# weather_station1.net
KiCad netlist of a schematic drawn in EAGLE
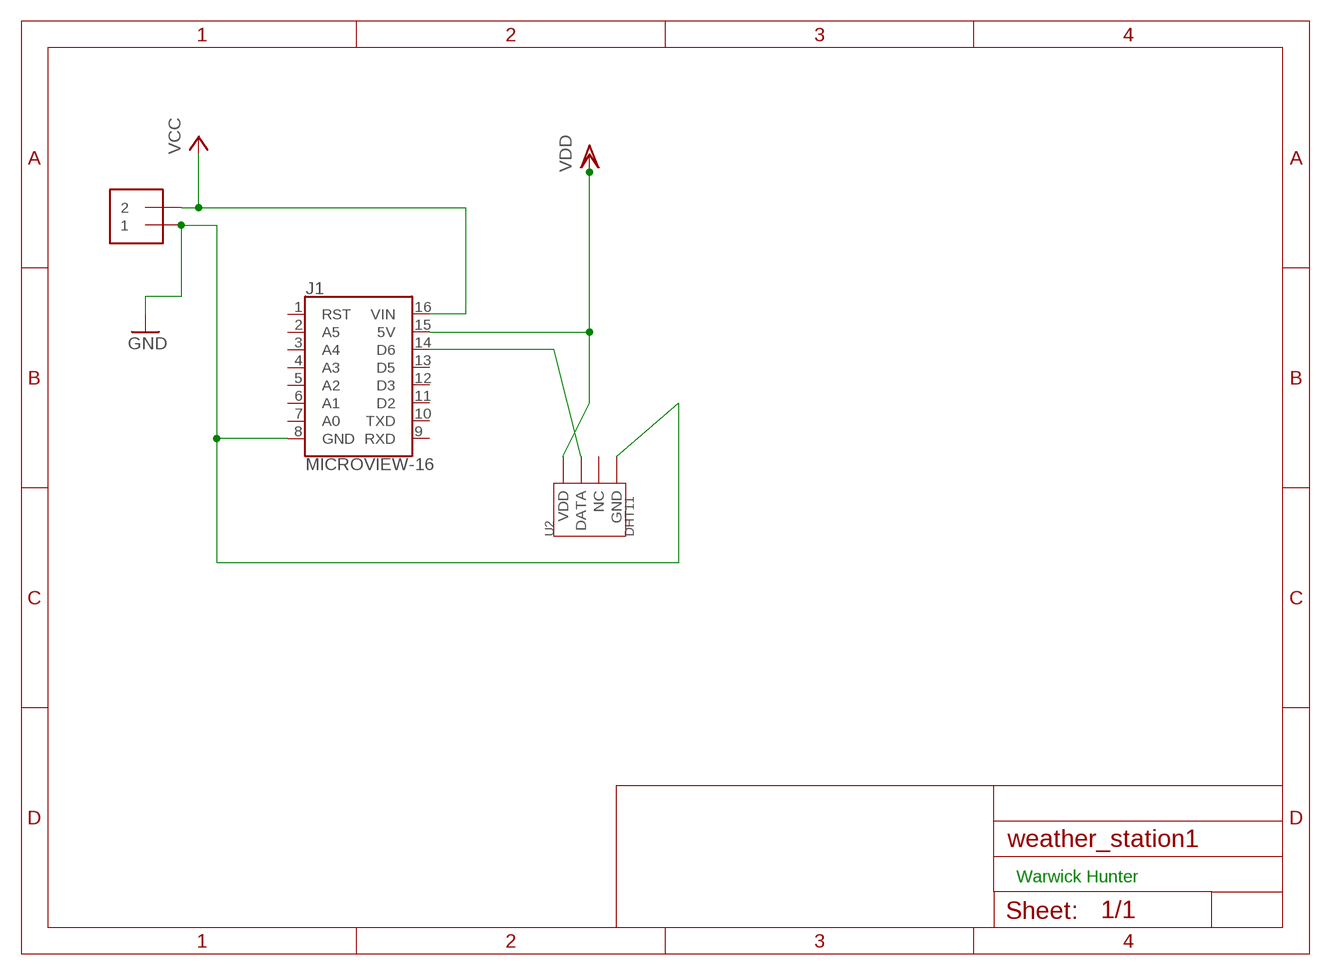
[diagram p0: schematic, sheet 1]

(export (version "E")
  (design (tool "Eeschema 10.0.6"))
  (components
    (comp (ref "J1")
      (value "MICROVIEW-16")
      (footprint "eagle-import:MV-DIP16")
      (libsource (lib "eagle-import") (part "MICROVIEW-16"))
    )
    (comp (ref "J2")
      (value "1X2-3.5MM")
      (footprint "eagle-import:1X2-3.5MM")
      (libsource (lib "eagle-import") (part "1X2-3.5MM"))
    )
    (comp (ref "U2")
      (value "DHT11")
      (footprint "eagle-import:SNR4-2.54-15.5X12.0X5.5MM")
      (libsource (lib "eagle-import") (part "TEM-HUM-DHT11(4P-15.5X12.0MM)"))
    )
  )
  (nets
    (net (code "1") (name "GND") (class "Default")
      (node (ref "J1") (pin "8") (pinfunction "GND_8") (pintype "output"))
      (node (ref "J2") (pin "1") (pinfunction "1_1") (pintype "passive"))
      (node (ref "U2") (pin "4") (pinfunction "GND_4") (pintype "power_in"))
    )
    (net (code "2") (name "Net-(J1-D6)") (class "Default")
      (node (ref "J1") (pin "14") (pinfunction "D6_14") (pintype "output"))
      (node (ref "U2") (pin "2") (pinfunction "DATA_2") (pintype "bidirectional"))
    )
    (net (code "3") (name "VCC") (class "Default")
      (node (ref "J1") (pin "16") (pinfunction "VIN_16") (pintype "output"))
      (node (ref "J2") (pin "2") (pinfunction "2_2") (pintype "passive"))
    )
    (net (code "4") (name "VDD") (class "Default")
      (node (ref "J1") (pin "15") (pinfunction "5V_15") (pintype "output"))
      (node (ref "U2") (pin "1") (pinfunction "VDD_1") (pintype "power_in"))
    )
    (net (code "5") (name "unconnected-(J1-A0-Pad7)") (class "Default")
      (node (ref "J1") (pin "7") (pinfunction "A0_7") (pintype "output"))
    )
    (net (code "6") (name "unconnected-(J1-A1-Pad6)") (class "Default")
      (node (ref "J1") (pin "6") (pinfunction "A1_6") (pintype "output"))
    )
    (net (code "7") (name "unconnected-(J1-A2-Pad5)") (class "Default")
      (node (ref "J1") (pin "5") (pinfunction "A2_5") (pintype "output"))
    )
    (net (code "8") (name "unconnected-(J1-A3-Pad4)") (class "Default")
      (node (ref "J1") (pin "4") (pinfunction "A3_4") (pintype "output"))
    )
    (net (code "9") (name "unconnected-(J1-A4-Pad3)") (class "Default")
      (node (ref "J1") (pin "3") (pinfunction "A4_3") (pintype "output"))
    )
    (net (code "10") (name "unconnected-(J1-A5-Pad2)") (class "Default")
      (node (ref "J1") (pin "2") (pinfunction "A5_2") (pintype "output"))
    )
    (net (code "11") (name "unconnected-(J1-D2-Pad11)") (class "Default")
      (node (ref "J1") (pin "11") (pinfunction "D2_11") (pintype "output"))
    )
    (net (code "12") (name "unconnected-(J1-D3-Pad12)") (class "Default")
      (node (ref "J1") (pin "12") (pinfunction "D3_12") (pintype "output"))
    )
    (net (code "13") (name "unconnected-(J1-D5-Pad13)") (class "Default")
      (node (ref "J1") (pin "13") (pinfunction "D5_13") (pintype "output"))
    )
    (net (code "14") (name "unconnected-(J1-RST-Pad1)") (class "Default")
      (node (ref "J1") (pin "1") (pinfunction "RST_1") (pintype "output"))
    )
    (net (code "15") (name "unconnected-(J1-RXD-Pad9)") (class "Default")
      (node (ref "J1") (pin "9") (pinfunction "RXD_9") (pintype "output"))
    )
    (net (code "16") (name "unconnected-(J1-TXD-Pad10)") (class "Default")
      (node (ref "J1") (pin "10") (pinfunction "TXD_10") (pintype "output"))
    )
    (net (code "17") (name "unconnected-(U2-NC-Pad3)") (class "Default")
      (node (ref "U2") (pin "3") (pinfunction "NC_3") (pintype "no_connect"))
    )
  )
)
